# rack.net
KiCad netlist of a schematic drawn in EAGLE
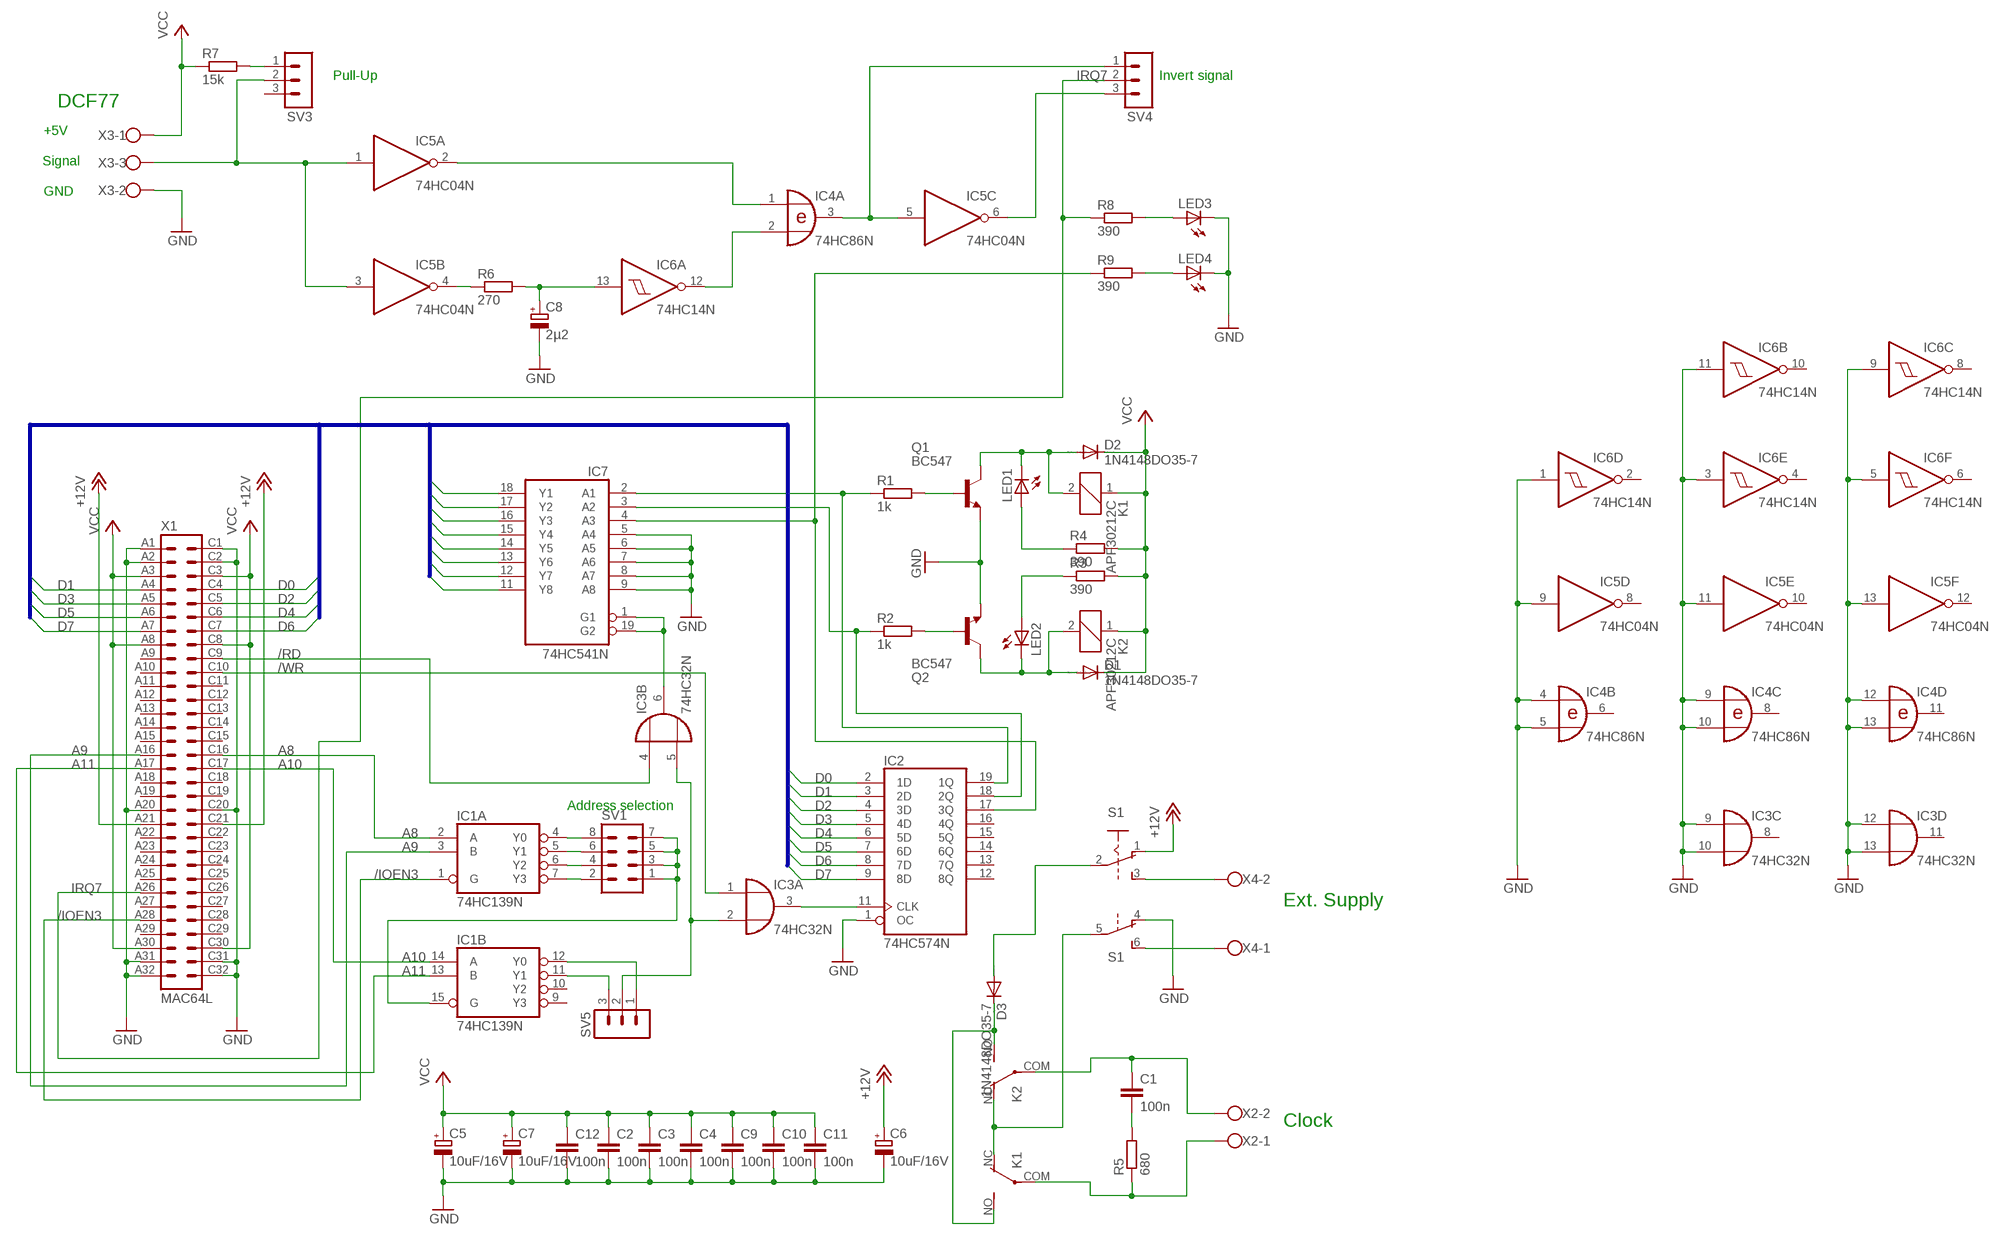
[diagram p0: schematic, sheet 1]

(export (version "E")
  (design (tool "Eeschema 10.0.6"))
  (components
    (comp (ref "C1")
      (value "100n")
      (footprint "eagle-import:C050-024X044")
      (libsource (lib "eagle-import") (part "C-EU050-024X044"))
    )
    (comp (ref "C2")
      (value "100n")
      (footprint "eagle-import:C050-024X044")
      (libsource (lib "eagle-import") (part "C-EU050-024X044"))
    )
    (comp (ref "C3")
      (value "100n")
      (footprint "eagle-import:C050-024X044")
      (libsource (lib "eagle-import") (part "C-EU050-024X044"))
    )
    (comp (ref "C4")
      (value "100n")
      (footprint "eagle-import:C050-024X044")
      (libsource (lib "eagle-import") (part "C-EU050-024X044"))
    )
    (comp (ref "C5")
      (value "10uF/16V")
      (footprint "eagle-import:TT2D5")
      (libsource (lib "eagle-import") (part "CPOL-EUTT2D5"))
    )
    (comp (ref "C6")
      (value "10uF/16V")
      (footprint "eagle-import:TT2D5")
      (libsource (lib "eagle-import") (part "CPOL-EUTT2D5"))
    )
    (comp (ref "C7")
      (value "10uF/16V")
      (footprint "eagle-import:TT2D5")
      (libsource (lib "eagle-import") (part "CPOL-EUTT2D5"))
    )
    (comp (ref "C8")
      (value "2µ2")
      (footprint "eagle-import:E2,5-6E")
      (libsource (lib "eagle-import") (part "CPOL-EUE2,5-6E"))
    )
    (comp (ref "C9")
      (value "100n")
      (footprint "eagle-import:C050-024X044")
      (libsource (lib "eagle-import") (part "C-EU050-024X044"))
    )
    (comp (ref "C10")
      (value "100n")
      (footprint "eagle-import:C050-024X044")
      (libsource (lib "eagle-import") (part "C-EU050-024X044"))
    )
    (comp (ref "C11")
      (value "100n")
      (footprint "eagle-import:C050-024X044")
      (libsource (lib "eagle-import") (part "C-EU050-024X044"))
    )
    (comp (ref "C12")
      (value "100n")
      (footprint "eagle-import:C050-024X044")
      (libsource (lib "eagle-import") (part "C-EU050-024X044"))
    )
    (comp (ref "D1")
      (value "1N4148DO35-7")
      (footprint "eagle-import:DO35-7")
      (libsource (lib "eagle-import") (part "1N4148DO35-7"))
    )
    (comp (ref "D2")
      (value "1N4148DO35-7")
      (footprint "eagle-import:DO35-7")
      (libsource (lib "eagle-import") (part "1N4148DO35-7"))
    )
    (comp (ref "D3")
      (value "1N4148DO35-7")
      (footprint "eagle-import:DO35-7")
      (libsource (lib "eagle-import") (part "1N4148DO35-7"))
    )
    (comp (ref "IC1")
      (value "74HC139N")
      (footprint "eagle-import:DIL16")
      (libsource (lib "eagle-import") (part "74139NHC"))
    )
    (comp (ref "IC2")
      (value "74HC574N")
      (footprint "eagle-import:DIL20")
      (libsource (lib "eagle-import") (part "74574NHC"))
    )
    (comp (ref "IC3")
      (value "74HC32N")
      (footprint "eagle-import:DIL14")
      (libsource (lib "eagle-import") (part "7432NHC"))
    )
    (comp (ref "IC4")
      (value "74HC86N")
      (footprint "eagle-import:DIL14")
      (libsource (lib "eagle-import") (part "7486NHC"))
    )
    (comp (ref "IC5")
      (value "74HC04N")
      (footprint "eagle-import:DIL14")
      (libsource (lib "eagle-import") (part "7404NHC"))
    )
    (comp (ref "IC6")
      (value "74HC14N")
      (footprint "eagle-import:DIL14")
      (libsource (lib "eagle-import") (part "7414NHC"))
    )
    (comp (ref "IC7")
      (value "74HC541N")
      (footprint "eagle-import:DIL20")
      (libsource (lib "eagle-import") (part "74541NHC"))
    )
    (comp (ref "K1")
      (value "APF30212C")
      (footprint "eagle-import:APF30212C")
      (libsource (lib "eagle-import") (part "APF30212C"))
    )
    (comp (ref "K2")
      (value "APF30212C")
      (footprint "eagle-import:APF30212C")
      (libsource (lib "eagle-import") (part "APF30212C"))
    )
    (comp (ref "LED1")
      (value "LEDB155")
      (footprint "eagle-import:Q62902-B155")
      (libsource (lib "eagle-import") (part "LEDB155"))
    )
    (comp (ref "LED2")
      (value "LEDB155")
      (footprint "eagle-import:Q62902-B155")
      (libsource (lib "eagle-import") (part "LEDB155"))
    )
    (comp (ref "LED3")
      (value "LEDB155")
      (footprint "eagle-import:Q62902-B155")
      (libsource (lib "eagle-import") (part "LEDB155"))
    )
    (comp (ref "LED4")
      (value "LEDB155")
      (footprint "eagle-import:Q62902-B155")
      (libsource (lib "eagle-import") (part "LEDB155"))
    )
    (comp (ref "Q1")
      (value "BC547")
      (footprint "eagle-import:TO92")
      (libsource (lib "eagle-import") (part "BC547"))
    )
    (comp (ref "Q2")
      (value "BC547")
      (footprint "eagle-import:TO92")
      (libsource (lib "eagle-import") (part "BC547"))
    )
    (comp (ref "R1")
      (value "1k")
      (footprint "eagle-import:0204_7")
      (libsource (lib "eagle-import") (part "R-EU_0204/7"))
    )
    (comp (ref "R2")
      (value "1k")
      (footprint "eagle-import:0204_7")
      (libsource (lib "eagle-import") (part "R-EU_0204/7"))
    )
    (comp (ref "R3")
      (value "390")
      (footprint "eagle-import:0204_7")
      (libsource (lib "eagle-import") (part "R-EU_0204/7"))
    )
    (comp (ref "R4")
      (value "390")
      (footprint "eagle-import:0204_7")
      (libsource (lib "eagle-import") (part "R-EU_0204/7"))
    )
    (comp (ref "R5")
      (value "680")
      (footprint "eagle-import:0204_7")
      (libsource (lib "eagle-import") (part "R-EU_0204/7"))
    )
    (comp (ref "R6")
      (value "270")
      (footprint "eagle-import:0204_7")
      (libsource (lib "eagle-import") (part "R-EU_0204/7"))
    )
    (comp (ref "R7")
      (value "15k")
      (footprint "eagle-import:0204_7")
      (libsource (lib "eagle-import") (part "R-EU_0204/7"))
    )
    (comp (ref "R8")
      (value "390")
      (footprint "eagle-import:0204_7")
      (libsource (lib "eagle-import") (part "R-EU_0204/7"))
    )
    (comp (ref "R9")
      (value "390")
      (footprint "eagle-import:0204_7")
      (libsource (lib "eagle-import") (part "R-EU_0204/7"))
    )
    (comp (ref "S1")
      (value "A68-A31")
      (footprint "eagle-import:A68-A31")
      (libsource (lib "eagle-import") (part "A68-A31"))
    )
    (comp (ref "SV1")
      (value "MA04-2")
      (footprint "eagle-import:MA04-2")
      (libsource (lib "eagle-import") (part "MA04-2"))
    )
    (comp (ref "SV3")
      (value "MA03-1")
      (footprint "eagle-import:MA03-1")
      (libsource (lib "eagle-import") (part "MA03-1"))
    )
    (comp (ref "SV4")
      (value "MA03-1")
      (footprint "eagle-import:MA03-1")
      (libsource (lib "eagle-import") (part "MA03-1"))
    )
    (comp (ref "SV5")
      (value "MA03-1")
      (footprint "eagle-import:MA03-1")
      (libsource (lib "eagle-import") (part "MA03-1"))
    )
    (comp (ref "X1")
      (value "MAC64L")
      (footprint "eagle-import:MAC64L")
      (libsource (lib "eagle-import") (part "MAC64L"))
    )
    (comp (ref "X2")
      (value "W237-102")
      (footprint "eagle-import:W237-102")
      (fields (field (name "MPN") "237-102"))
      (libsource (lib "eagle-import") (part "W237-102"))
    )
    (comp (ref "X3")
      (value "W237-103")
      (footprint "eagle-import:W237-103")
      (fields (field (name "MPN") "237-103"))
      (libsource (lib "eagle-import") (part "W237-103"))
    )
    (comp (ref "X4")
      (value "W237-102")
      (footprint "eagle-import:W237-102")
      (fields (field (name "MPN") "237-102"))
      (libsource (lib "eagle-import") (part "W237-102"))
    )
  )
  (nets
    (net (code "1") (name "+12V") (class "Default")
      (node (ref "C6") (pin "+") (pinfunction "+_+") (pintype "passive"))
      (node (ref "S1") (pin "1") (pinfunction "O_1") (pintype "passive"))
      (node (ref "X1") (pin "A21") (pinfunction "A21_A21") (pintype "passive"))
      (node (ref "X1") (pin "C21") (pinfunction "C21_C21") (pintype "passive"))
    )
    (net (code "2") (name "/A8") (class "Default")
      (node (ref "IC1") (pin "2") (pinfunction "A_2") (pintype "input"))
      (node (ref "X1") (pin "C16") (pinfunction "C16_C16") (pintype "passive"))
    )
    (net (code "3") (name "/A9") (class "Default")
      (node (ref "IC1") (pin "3") (pinfunction "B_3") (pintype "input"))
      (node (ref "X1") (pin "A16") (pinfunction "A16_A16") (pintype "passive"))
    )
    (net (code "4") (name "/A10") (class "Default")
      (node (ref "IC1") (pin "14") (pinfunction "A_14") (pintype "input"))
      (node (ref "X1") (pin "C17") (pinfunction "C17_C17") (pintype "passive"))
    )
    (net (code "5") (name "/A11") (class "Default")
      (node (ref "IC1") (pin "13") (pinfunction "B_13") (pintype "input"))
      (node (ref "X1") (pin "A17") (pinfunction "A17_A17") (pintype "passive"))
    )
    (net (code "6") (name "/D0") (class "Default")
      (node (ref "IC2") (pin "2") (pinfunction "1D_2") (pintype "input"))
      (node (ref "IC7") (pin "18") (pinfunction "Y1_18") (pintype "tri_state"))
      (node (ref "X1") (pin "C4") (pinfunction "C4_C4") (pintype "passive"))
    )
    (net (code "7") (name "/D1") (class "Default")
      (node (ref "IC2") (pin "3") (pinfunction "2D_3") (pintype "input"))
      (node (ref "IC7") (pin "17") (pinfunction "Y2_17") (pintype "tri_state"))
      (node (ref "X1") (pin "A4") (pinfunction "A4_A4") (pintype "passive"))
    )
    (net (code "8") (name "/D2") (class "Default")
      (node (ref "IC2") (pin "4") (pinfunction "3D_4") (pintype "input"))
      (node (ref "IC7") (pin "16") (pinfunction "Y3_16") (pintype "tri_state"))
      (node (ref "X1") (pin "C5") (pinfunction "C5_C5") (pintype "passive"))
    )
    (net (code "9") (name "/D3") (class "Default")
      (node (ref "IC2") (pin "5") (pinfunction "4D_5") (pintype "input"))
      (node (ref "IC7") (pin "15") (pinfunction "Y4_15") (pintype "tri_state"))
      (node (ref "X1") (pin "A5") (pinfunction "A5_A5") (pintype "passive"))
    )
    (net (code "10") (name "/D4") (class "Default")
      (node (ref "IC2") (pin "6") (pinfunction "5D_6") (pintype "input"))
      (node (ref "IC7") (pin "14") (pinfunction "Y5_14") (pintype "tri_state"))
      (node (ref "X1") (pin "C6") (pinfunction "C6_C6") (pintype "passive"))
    )
    (net (code "11") (name "/D5") (class "Default")
      (node (ref "IC2") (pin "7") (pinfunction "6D_7") (pintype "input"))
      (node (ref "IC7") (pin "13") (pinfunction "Y6_13") (pintype "tri_state"))
      (node (ref "X1") (pin "A6") (pinfunction "A6_A6") (pintype "passive"))
    )
    (net (code "12") (name "/D6") (class "Default")
      (node (ref "IC2") (pin "8") (pinfunction "7D_8") (pintype "input"))
      (node (ref "IC7") (pin "12") (pinfunction "Y7_12") (pintype "tri_state"))
      (node (ref "X1") (pin "C7") (pinfunction "C7_C7") (pintype "passive"))
    )
    (net (code "13") (name "/D7") (class "Default")
      (node (ref "IC2") (pin "9") (pinfunction "8D_9") (pintype "input"))
      (node (ref "IC7") (pin "11") (pinfunction "Y8_11") (pintype "tri_state"))
      (node (ref "X1") (pin "A7") (pinfunction "A7_A7") (pintype "passive"))
    )
    (net (code "14") (name "/IRQ7") (class "Default")
      (node (ref "R8") (pin "1") (pinfunction "1_1") (pintype "passive"))
      (node (ref "SV4") (pin "2") (pinfunction "2_2") (pintype "passive"))
      (node (ref "X1") (pin "A26") (pinfunction "A26_A26") (pintype "passive"))
    )
    (net (code "15") (name "/{slash}IOEN3") (class "Default")
      (node (ref "IC1") (pin "1") (pinfunction "G_1") (pintype "input"))
      (node (ref "X1") (pin "A28") (pinfunction "A28_A28") (pintype "passive"))
    )
    (net (code "16") (name "/{slash}RD") (class "Default")
      (node (ref "IC3") (pin "4") (pinfunction "I0_4") (pintype "input"))
      (node (ref "X1") (pin "C9") (pinfunction "C9_C9") (pintype "passive"))
    )
    (net (code "17") (name "/{slash}WR") (class "Default")
      (node (ref "IC3") (pin "1") (pinfunction "I0_1") (pintype "input"))
      (node (ref "X1") (pin "C10") (pinfunction "C10_C10") (pintype "passive"))
    )
    (net (code "18") (name "GND") (class "Default")
      (node (ref "C10") (pin "2") (pinfunction "2_2") (pintype "passive"))
      (node (ref "C11") (pin "2") (pinfunction "2_2") (pintype "passive"))
      (node (ref "C12") (pin "2") (pinfunction "2_2") (pintype "passive"))
      (node (ref "C2") (pin "2") (pinfunction "2_2") (pintype "passive"))
      (node (ref "C3") (pin "2") (pinfunction "2_2") (pintype "passive"))
      (node (ref "C4") (pin "2") (pinfunction "2_2") (pintype "passive"))
      (node (ref "C5") (pin "-") (pinfunction "-_-") (pintype "passive"))
      (node (ref "C6") (pin "-") (pinfunction "-_-") (pintype "passive"))
      (node (ref "C7") (pin "-") (pinfunction "-_-") (pintype "passive"))
      (node (ref "C8") (pin "-") (pinfunction "-_-") (pintype "passive"))
      (node (ref "C9") (pin "2") (pinfunction "2_2") (pintype "passive"))
      (node (ref "IC2") (pin "1") (pinfunction "OC_1") (pintype "input"))
      (node (ref "IC3") (pin "10") (pinfunction "I1_10") (pintype "input"))
      (node (ref "IC3") (pin "12") (pinfunction "I0_12") (pintype "input"))
      (node (ref "IC3") (pin "13") (pinfunction "I1_13") (pintype "input"))
      (node (ref "IC3") (pin "9") (pinfunction "I0_9") (pintype "input"))
      (node (ref "IC4") (pin "10") (pinfunction "I1_10") (pintype "input"))
      (node (ref "IC4") (pin "12") (pinfunction "I0_12") (pintype "input"))
      (node (ref "IC4") (pin "13") (pinfunction "I1_13") (pintype "input"))
      (node (ref "IC4") (pin "4") (pinfunction "I0_4") (pintype "input"))
      (node (ref "IC4") (pin "5") (pinfunction "I1_5") (pintype "input"))
      (node (ref "IC4") (pin "9") (pinfunction "I0_9") (pintype "input"))
      (node (ref "IC5") (pin "11") (pinfunction "I_11") (pintype "input"))
      (node (ref "IC5") (pin "13") (pinfunction "I_13") (pintype "input"))
      (node (ref "IC5") (pin "9") (pinfunction "I_9") (pintype "input"))
      (node (ref "IC6") (pin "1") (pinfunction "I_1") (pintype "input"))
      (node (ref "IC6") (pin "11") (pinfunction "I_11") (pintype "input"))
      (node (ref "IC6") (pin "3") (pinfunction "I_3") (pintype "input"))
      (node (ref "IC6") (pin "5") (pinfunction "I_5") (pintype "input"))
      (node (ref "IC6") (pin "9") (pinfunction "I_9") (pintype "input"))
      (node (ref "IC7") (pin "5") (pinfunction "A4_5") (pintype "input"))
      (node (ref "IC7") (pin "6") (pinfunction "A5_6") (pintype "input"))
      (node (ref "IC7") (pin "7") (pinfunction "A6_7") (pintype "input"))
      (node (ref "IC7") (pin "8") (pinfunction "A7_8") (pintype "input"))
      (node (ref "IC7") (pin "9") (pinfunction "A8_9") (pintype "input"))
      (node (ref "LED3") (pin "K") (pinfunction "C_K") (pintype "passive"))
      (node (ref "LED4") (pin "K") (pinfunction "C_K") (pintype "passive"))
      (node (ref "Q1") (pin "1") (pinfunction "E_1") (pintype "passive"))
      (node (ref "Q2") (pin "1") (pinfunction "E_1") (pintype "passive"))
      (node (ref "S1") (pin "4") (pinfunction "O_4") (pintype "passive"))
      (node (ref "X1") (pin "A1") (pinfunction "A1_A1") (pintype "passive"))
      (node (ref "X1") (pin "A2") (pinfunction "A2_A2") (pintype "passive"))
      (node (ref "X1") (pin "A20") (pinfunction "A20_A20") (pintype "passive"))
      (node (ref "X1") (pin "A31") (pinfunction "A31_A31") (pintype "passive"))
      (node (ref "X1") (pin "A32") (pinfunction "A32_A32") (pintype "passive"))
      (node (ref "X1") (pin "C1") (pinfunction "C1_C1") (pintype "passive"))
      (node (ref "X1") (pin "C2") (pinfunction "C2_C2") (pintype "passive"))
      (node (ref "X1") (pin "C20") (pinfunction "C20_C20") (pintype "passive"))
      (node (ref "X1") (pin "C31") (pinfunction "C31_C31") (pintype "passive"))
      (node (ref "X1") (pin "C32") (pinfunction "C32_C32") (pintype "passive"))
      (node (ref "X3") (pin "2") (pinfunction "KL_2") (pintype "passive"))
    )
    (net (code "19") (name "Net-(C1-Pad2)") (class "Default")
      (node (ref "C1") (pin "2") (pinfunction "2_2") (pintype "passive"))
      (node (ref "R5") (pin "2") (pinfunction "2_2") (pintype "passive"))
    )
    (net (code "20") (name "Net-(IC1A-Y0)") (class "Default")
      (node (ref "IC1") (pin "4") (pinfunction "Y0_4") (pintype "output"))
      (node (ref "SV1") (pin "8") (pinfunction "8_8") (pintype "passive"))
    )
    (net (code "21") (name "Net-(IC1A-Y1)") (class "Default")
      (node (ref "IC1") (pin "5") (pinfunction "Y1_5") (pintype "output"))
      (node (ref "SV1") (pin "6") (pinfunction "6_6") (pintype "passive"))
    )
    (net (code "22") (name "Net-(IC1A-Y2)") (class "Default")
      (node (ref "IC1") (pin "6") (pinfunction "Y2_6") (pintype "output"))
      (node (ref "SV1") (pin "4") (pinfunction "4_4") (pintype "passive"))
    )
    (net (code "23") (name "Net-(IC1A-Y3)") (class "Default")
      (node (ref "IC1") (pin "7") (pinfunction "Y3_7") (pintype "output"))
      (node (ref "SV1") (pin "2") (pinfunction "2_2") (pintype "passive"))
    )
    (net (code "24") (name "Net-(IC1B-G)") (class "Default")
      (node (ref "IC1") (pin "15") (pinfunction "G_15") (pintype "input"))
      (node (ref "SV1") (pin "1") (pinfunction "1_1") (pintype "passive"))
      (node (ref "SV1") (pin "3") (pinfunction "3_3") (pintype "passive"))
      (node (ref "SV1") (pin "5") (pinfunction "5_5") (pintype "passive"))
      (node (ref "SV1") (pin "7") (pinfunction "7_7") (pintype "passive"))
    )
    (net (code "25") (name "Net-(IC1B-Y0)") (class "Default")
      (node (ref "IC1") (pin "12") (pinfunction "Y0_12") (pintype "output"))
      (node (ref "SV5") (pin "1") (pinfunction "1_1") (pintype "passive"))
    )
    (net (code "26") (name "Net-(IC1B-Y1)") (class "Default")
      (node (ref "IC1") (pin "11") (pinfunction "Y1_11") (pintype "output"))
      (node (ref "SV5") (pin "3") (pinfunction "3_3") (pintype "passive"))
    )
    (net (code "27") (name "Net-(IC2A-1Q)") (class "Default")
      (node (ref "IC2") (pin "19") (pinfunction "1Q_19") (pintype "tri_state"))
      (node (ref "IC7") (pin "2") (pinfunction "A1_2") (pintype "input"))
      (node (ref "R1") (pin "1") (pinfunction "1_1") (pintype "passive"))
    )
    (net (code "28") (name "Net-(IC2A-2Q)") (class "Default")
      (node (ref "IC2") (pin "18") (pinfunction "2Q_18") (pintype "tri_state"))
      (node (ref "IC7") (pin "3") (pinfunction "A2_3") (pintype "input"))
      (node (ref "R2") (pin "1") (pinfunction "1_1") (pintype "passive"))
    )
    (net (code "29") (name "Net-(IC2A-3Q)") (class "Default")
      (node (ref "IC2") (pin "17") (pinfunction "3Q_17") (pintype "tri_state"))
      (node (ref "IC7") (pin "4") (pinfunction "A3_4") (pintype "input"))
      (node (ref "R9") (pin "1") (pinfunction "1_1") (pintype "passive"))
    )
    (net (code "30") (name "Net-(IC2A-CLK)") (class "Default")
      (node (ref "IC2") (pin "11") (pinfunction "CLK_11") (pintype "input"))
      (node (ref "IC3") (pin "3") (pinfunction "O_3") (pintype "output"))
    )
    (net (code "31") (name "Net-(IC3A-I1)") (class "Default")
      (node (ref "IC3") (pin "2") (pinfunction "I1_2") (pintype "input"))
      (node (ref "IC3") (pin "5") (pinfunction "I1_5") (pintype "input"))
      (node (ref "SV5") (pin "2") (pinfunction "2_2") (pintype "passive"))
    )
    (net (code "32") (name "Net-(IC3B-O)") (class "Default")
      (node (ref "IC3") (pin "6") (pinfunction "O_6") (pintype "output"))
      (node (ref "IC7") (pin "1") (pinfunction "G1_1") (pintype "input"))
      (node (ref "IC7") (pin "19") (pinfunction "G2_19") (pintype "input"))
    )
    (net (code "33") (name "Net-(IC4A-I0)") (class "Default")
      (node (ref "IC4") (pin "1") (pinfunction "I0_1") (pintype "input"))
      (node (ref "IC5") (pin "2") (pinfunction "O_2") (pintype "output"))
    )
    (net (code "34") (name "Net-(IC4A-I1)") (class "Default")
      (node (ref "IC4") (pin "2") (pinfunction "I1_2") (pintype "input"))
      (node (ref "IC6") (pin "12") (pinfunction "O_12") (pintype "output"))
    )
    (net (code "35") (name "Net-(IC4A-O)") (class "Default")
      (node (ref "IC4") (pin "3") (pinfunction "O_3") (pintype "output"))
      (node (ref "IC5") (pin "5") (pinfunction "I_5") (pintype "input"))
      (node (ref "SV4") (pin "1") (pinfunction "1_1") (pintype "passive"))
    )
    (net (code "36") (name "Net-(IC5A-I)") (class "Default")
      (node (ref "IC5") (pin "1") (pinfunction "I_1") (pintype "input"))
      (node (ref "IC5") (pin "3") (pinfunction "I_3") (pintype "input"))
      (node (ref "SV3") (pin "2") (pinfunction "2_2") (pintype "passive"))
      (node (ref "X3") (pin "3") (pinfunction "KL_3") (pintype "passive"))
    )
    (net (code "37") (name "Net-(IC5B-O)") (class "Default")
      (node (ref "IC5") (pin "4") (pinfunction "O_4") (pintype "output"))
      (node (ref "R6") (pin "1") (pinfunction "1_1") (pintype "passive"))
    )
    (net (code "38") (name "Net-(IC5C-O)") (class "Default")
      (node (ref "IC5") (pin "6") (pinfunction "O_6") (pintype "output"))
      (node (ref "SV4") (pin "3") (pinfunction "3_3") (pintype "passive"))
    )
    (net (code "39") (name "Net-(IC6A-I)") (class "Default")
      (node (ref "C8") (pin "+") (pinfunction "+_+") (pintype "passive"))
      (node (ref "IC6") (pin "13") (pinfunction "I_13") (pintype "input"))
      (node (ref "R6") (pin "2") (pinfunction "2_2") (pintype "passive"))
    )
    (net (code "40") (name "Net-(K1B-O)") (class "Default")
      (node (ref "K1") (pin "NC") (pinfunction "O_NC") (pintype "passive"))
      (node (ref "K2") (pin "NC") (pinfunction "O_NC") (pintype "passive"))
      (node (ref "S1") (pin "5") (pinfunction "P_5") (pintype "passive"))
    )
    (net (code "41") (name "Net-(K1B-P)") (class "Default")
      (node (ref "K1") (pin "COM") (pinfunction "P_COM") (pintype "passive"))
      (node (ref "R5") (pin "1") (pinfunction "1_1") (pintype "passive"))
      (node (ref "X2") (pin "1") (pinfunction "KL_1") (pintype "passive"))
    )
    (net (code "42") (name "Net-(K1B-S)") (class "Default")
      (node (ref "D3") (pin "C") (pinfunction "C_C") (pintype "passive"))
      (node (ref "K1") (pin "NO") (pinfunction "S_NO") (pintype "passive"))
      (node (ref "K2") (pin "NO") (pinfunction "S_NO") (pintype "passive"))
    )
    (net (code "43") (name "Net-(K2B-P)") (class "Default")
      (node (ref "C1") (pin "1") (pinfunction "1_1") (pintype "passive"))
      (node (ref "K2") (pin "COM") (pinfunction "P_COM") (pintype "passive"))
      (node (ref "X2") (pin "2") (pinfunction "KL_2") (pintype "passive"))
    )
    (net (code "44") (name "Net-(LED1-C)") (class "Default")
      (node (ref "D2") (pin "A") (pinfunction "A_A") (pintype "passive"))
      (node (ref "K1") (pin "2") (pinfunction "2_2") (pintype "passive"))
      (node (ref "LED1") (pin "K") (pinfunction "C_K") (pintype "passive"))
      (node (ref "Q1") (pin "3") (pinfunction "C_3") (pintype "passive"))
    )
    (net (code "45") (name "Net-(LED1-PadA)") (class "Default")
      (node (ref "LED1") (pin "A") (pinfunction "A_A") (pintype "passive"))
      (node (ref "R4") (pin "1") (pinfunction "1_1") (pintype "passive"))
    )
    (net (code "46") (name "Net-(LED2-C)") (class "Default")
      (node (ref "D1") (pin "A") (pinfunction "A_A") (pintype "passive"))
      (node (ref "K2") (pin "2") (pinfunction "2_2") (pintype "passive"))
      (node (ref "LED2") (pin "K") (pinfunction "C_K") (pintype "passive"))
      (node (ref "Q2") (pin "3") (pinfunction "C_3") (pintype "passive"))
    )
    (net (code "47") (name "Net-(LED2-PadA)") (class "Default")
      (node (ref "LED2") (pin "A") (pinfunction "A_A") (pintype "passive"))
      (node (ref "R3") (pin "1") (pinfunction "1_1") (pintype "passive"))
    )
    (net (code "48") (name "Net-(LED3-PadA)") (class "Default")
      (node (ref "LED3") (pin "A") (pinfunction "A_A") (pintype "passive"))
      (node (ref "R8") (pin "2") (pinfunction "2_2") (pintype "passive"))
    )
    (net (code "49") (name "Net-(LED4-PadA)") (class "Default")
      (node (ref "LED4") (pin "A") (pinfunction "A_A") (pintype "passive"))
      (node (ref "R9") (pin "2") (pinfunction "2_2") (pintype "passive"))
    )
    (net (code "50") (name "Net-(Q1-B)") (class "Default")
      (node (ref "Q1") (pin "2") (pinfunction "B_2") (pintype "passive"))
      (node (ref "R1") (pin "2") (pinfunction "2_2") (pintype "passive"))
    )
    (net (code "51") (name "Net-(Q2-B)") (class "Default")
      (node (ref "Q2") (pin "2") (pinfunction "B_2") (pintype "passive"))
      (node (ref "R2") (pin "2") (pinfunction "2_2") (pintype "passive"))
    )
    (net (code "52") (name "Net-(R7-Pad2)") (class "Default")
      (node (ref "R7") (pin "2") (pinfunction "2_2") (pintype "passive"))
      (node (ref "SV3") (pin "1") (pinfunction "1_1") (pintype "passive"))
    )
    (net (code "53") (name "Net-(S1A-P)") (class "Default")
      (node (ref "D3") (pin "A") (pinfunction "A_A") (pintype "passive"))
      (node (ref "S1") (pin "2") (pinfunction "P_2") (pintype "passive"))
    )
    (net (code "54") (name "Net-(S1A-S)") (class "Default")
      (node (ref "S1") (pin "3") (pinfunction "S_3") (pintype "passive"))
      (node (ref "X4") (pin "2") (pinfunction "KL_2") (pintype "passive"))
    )
    (net (code "55") (name "Net-(S1B-S)") (class "Default")
      (node (ref "S1") (pin "6") (pinfunction "S_6") (pintype "passive"))
      (node (ref "X4") (pin "1") (pinfunction "KL_1") (pintype "passive"))
    )
    (net (code "56") (name "VCC") (class "Default")
      (node (ref "C10") (pin "1") (pinfunction "1_1") (pintype "passive"))
      (node (ref "C11") (pin "1") (pinfunction "1_1") (pintype "passive"))
      (node (ref "C12") (pin "1") (pinfunction "1_1") (pintype "passive"))
      (node (ref "C2") (pin "1") (pinfunction "1_1") (pintype "passive"))
      (node (ref "C3") (pin "1") (pinfunction "1_1") (pintype "passive"))
      (node (ref "C4") (pin "1") (pinfunction "1_1") (pintype "passive"))
      (node (ref "C5") (pin "+") (pinfunction "+_+") (pintype "passive"))
      (node (ref "C7") (pin "+") (pinfunction "+_+") (pintype "passive"))
      (node (ref "C9") (pin "1") (pinfunction "1_1") (pintype "passive"))
      (node (ref "D1") (pin "C") (pinfunction "C_C") (pintype "passive"))
      (node (ref "D2") (pin "C") (pinfunction "C_C") (pintype "passive"))
      (node (ref "K1") (pin "1") (pinfunction "1_1") (pintype "passive"))
      (node (ref "K2") (pin "1") (pinfunction "1_1") (pintype "passive"))
      (node (ref "R3") (pin "2") (pinfunction "2_2") (pintype "passive"))
      (node (ref "R4") (pin "2") (pinfunction "2_2") (pintype "passive"))
      (node (ref "R7") (pin "1") (pinfunction "1_1") (pintype "passive"))
      (node (ref "X1") (pin "A3") (pinfunction "A3_A3") (pintype "passive"))
      (node (ref "X1") (pin "A30") (pinfunction "A30_A30") (pintype "passive"))
      (node (ref "X1") (pin "A8") (pinfunction "A8_A8") (pintype "passive"))
      (node (ref "X1") (pin "C3") (pinfunction "C3_C3") (pintype "passive"))
      (node (ref "X1") (pin "C30") (pinfunction "C30_C30") (pintype "passive"))
      (node (ref "X1") (pin "C8") (pinfunction "C8_C8") (pintype "passive"))
      (node (ref "X3") (pin "1") (pinfunction "KL_1") (pintype "passive"))
    )
    (net (code "57") (name "unconnected-(IC1B-Y2-Pad10)") (class "Default")
      (node (ref "IC1") (pin "10") (pinfunction "Y2_10") (pintype "output"))
    )
    (net (code "58") (name "unconnected-(IC1B-Y3-Pad9)") (class "Default")
      (node (ref "IC1") (pin "9") (pinfunction "Y3_9") (pintype "output"))
    )
    (net (code "59") (name "unconnected-(IC2A-4Q-Pad16)") (class "Default")
      (node (ref "IC2") (pin "16") (pinfunction "4Q_16") (pintype "tri_state"))
    )
    (net (code "60") (name "unconnected-(IC2A-5Q-Pad15)") (class "Default")
      (node (ref "IC2") (pin "15") (pinfunction "5Q_15") (pintype "tri_state"))
    )
    (net (code "61") (name "unconnected-(IC2A-6Q-Pad14)") (class "Default")
      (node (ref "IC2") (pin "14") (pinfunction "6Q_14") (pintype "tri_state"))
    )
    (net (code "62") (name "unconnected-(IC2A-7Q-Pad13)") (class "Default")
      (node (ref "IC2") (pin "13") (pinfunction "7Q_13") (pintype "tri_state"))
    )
    (net (code "63") (name "unconnected-(IC2A-8Q-Pad12)") (class "Default")
      (node (ref "IC2") (pin "12") (pinfunction "8Q_12") (pintype "tri_state"))
    )
    (net (code "64") (name "unconnected-(IC3C-O-Pad8)") (class "Default")
      (node (ref "IC3") (pin "8") (pinfunction "O_8") (pintype "output"))
    )
    (net (code "65") (name "unconnected-(IC3D-O-Pad11)") (class "Default")
      (node (ref "IC3") (pin "11") (pinfunction "O_11") (pintype "output"))
    )
    (net (code "66") (name "unconnected-(IC4B-O-Pad6)") (class "Default")
      (node (ref "IC4") (pin "6") (pinfunction "O_6") (pintype "output"))
    )
    (net (code "67") (name "unconnected-(IC4C-O-Pad8)") (class "Default")
      (node (ref "IC4") (pin "8") (pinfunction "O_8") (pintype "output"))
    )
    (net (code "68") (name "unconnected-(IC4D-O-Pad11)") (class "Default")
      (node (ref "IC4") (pin "11") (pinfunction "O_11") (pintype "output"))
    )
    (net (code "69") (name "unconnected-(IC5D-O-Pad8)") (class "Default")
      (node (ref "IC5") (pin "8") (pinfunction "O_8") (pintype "output"))
    )
    (net (code "70") (name "unconnected-(IC5E-O-Pad10)") (class "Default")
      (node (ref "IC5") (pin "10") (pinfunction "O_10") (pintype "output"))
    )
    (net (code "71") (name "unconnected-(IC5F-O-Pad12)") (class "Default")
      (node (ref "IC5") (pin "12") (pinfunction "O_12") (pintype "output"))
    )
    (net (code "72") (name "unconnected-(IC6B-O-Pad10)") (class "Default")
      (node (ref "IC6") (pin "10") (pinfunction "O_10") (pintype "output"))
    )
    (net (code "73") (name "unconnected-(IC6C-O-Pad8)") (class "Default")
      (node (ref "IC6") (pin "8") (pinfunction "O_8") (pintype "output"))
    )
    (net (code "74") (name "unconnected-(IC6D-O-Pad2)") (class "Default")
      (node (ref "IC6") (pin "2") (pinfunction "O_2") (pintype "output"))
    )
    (net (code "75") (name "unconnected-(IC6E-O-Pad4)") (class "Default")
      (node (ref "IC6") (pin "4") (pinfunction "O_4") (pintype "output"))
    )
    (net (code "76") (name "unconnected-(IC6F-O-Pad6)") (class "Default")
      (node (ref "IC6") (pin "6") (pinfunction "O_6") (pintype "output"))
    )
    (net (code "77") (name "unconnected-(SV3-Pad3)") (class "Default")
      (node (ref "SV3") (pin "3") (pinfunction "3_3") (pintype "passive"))
    )
    (net (code "78") (name "unconnected-(X1-PadA9)") (class "Default")
      (node (ref "X1") (pin "A9") (pinfunction "A9_A9") (pintype "passive"))
    )
    (net (code "79") (name "unconnected-(X1-PadA10)") (class "Default")
      (node (ref "X1") (pin "A10") (pinfunction "A10_A10") (pintype "passive"))
    )
    (net (code "80") (name "unconnected-(X1-PadA11)") (class "Default")
      (node (ref "X1") (pin "A11") (pinfunction "A11_A11") (pintype "passive"))
    )
    (net (code "81") (name "unconnected-(X1-PadA12)") (class "Default")
      (node (ref "X1") (pin "A12") (pinfunction "A12_A12") (pintype "passive"))
    )
    (net (code "82") (name "unconnected-(X1-PadA13)") (class "Default")
      (node (ref "X1") (pin "A13") (pinfunction "A13_A13") (pintype "passive"))
    )
    (net (code "83") (name "unconnected-(X1-PadA14)") (class "Default")
      (node (ref "X1") (pin "A14") (pinfunction "A14_A14") (pintype "passive"))
    )
    (net (code "84") (name "unconnected-(X1-PadA15)") (class "Default")
      (node (ref "X1") (pin "A15") (pinfunction "A15_A15") (pintype "passive"))
    )
    (net (code "85") (name "unconnected-(X1-PadA18)") (class "Default")
      (node (ref "X1") (pin "A18") (pinfunction "A18_A18") (pintype "passive"))
    )
    (net (code "86") (name "unconnected-(X1-PadA19)") (class "Default")
      (node (ref "X1") (pin "A19") (pinfunction "A19_A19") (pintype "passive"))
    )
    (net (code "87") (name "unconnected-(X1-PadA22)") (class "Default")
      (node (ref "X1") (pin "A22") (pinfunction "A22_A22") (pintype "passive"))
    )
    (net (code "88") (name "unconnected-(X1-PadA23)") (class "Default")
      (node (ref "X1") (pin "A23") (pinfunction "A23_A23") (pintype "passive"))
    )
    (net (code "89") (name "unconnected-(X1-PadA24)") (class "Default")
      (node (ref "X1") (pin "A24") (pinfunction "A24_A24") (pintype "passive"))
    )
    (net (code "90") (name "unconnected-(X1-PadA25)") (class "Default")
      (node (ref "X1") (pin "A25") (pinfunction "A25_A25") (pintype "passive"))
    )
    (net (code "91") (name "unconnected-(X1-PadA27)") (class "Default")
      (node (ref "X1") (pin "A27") (pinfunction "A27_A27") (pintype "passive"))
    )
    (net (code "92") (name "unconnected-(X1-PadA29)") (class "Default")
      (node (ref "X1") (pin "A29") (pinfunction "A29_A29") (pintype "passive"))
    )
    (net (code "93") (name "unconnected-(X1-PadC11)") (class "Default")
      (node (ref "X1") (pin "C11") (pinfunction "C11_C11") (pintype "passive"))
    )
    (net (code "94") (name "unconnected-(X1-PadC12)") (class "Default")
      (node (ref "X1") (pin "C12") (pinfunction "C12_C12") (pintype "passive"))
    )
    (net (code "95") (name "unconnected-(X1-PadC13)") (class "Default")
      (node (ref "X1") (pin "C13") (pinfunction "C13_C13") (pintype "passive"))
    )
    (net (code "96") (name "unconnected-(X1-PadC14)") (class "Default")
      (node (ref "X1") (pin "C14") (pinfunction "C14_C14") (pintype "passive"))
    )
    (net (code "97") (name "unconnected-(X1-PadC15)") (class "Default")
      (node (ref "X1") (pin "C15") (pinfunction "C15_C15") (pintype "passive"))
    )
    (net (code "98") (name "unconnected-(X1-PadC18)") (class "Default")
      (node (ref "X1") (pin "C18") (pinfunction "C18_C18") (pintype "passive"))
    )
    (net (code "99") (name "unconnected-(X1-PadC19)") (class "Default")
      (node (ref "X1") (pin "C19") (pinfunction "C19_C19") (pintype "passive"))
    )
    (net (code "100") (name "unconnected-(X1-PadC22)") (class "Default")
      (node (ref "X1") (pin "C22") (pinfunction "C22_C22") (pintype "passive"))
    )
    (net (code "101") (name "unconnected-(X1-PadC23)") (class "Default")
      (node (ref "X1") (pin "C23") (pinfunction "C23_C23") (pintype "passive"))
    )
    (net (code "102") (name "unconnected-(X1-PadC24)") (class "Default")
      (node (ref "X1") (pin "C24") (pinfunction "C24_C24") (pintype "passive"))
    )
    (net (code "103") (name "unconnected-(X1-PadC25)") (class "Default")
      (node (ref "X1") (pin "C25") (pinfunction "C25_C25") (pintype "passive"))
    )
    (net (code "104") (name "unconnected-(X1-PadC26)") (class "Default")
      (node (ref "X1") (pin "C26") (pinfunction "C26_C26") (pintype "passive"))
    )
    (net (code "105") (name "unconnected-(X1-PadC27)") (class "Default")
      (node (ref "X1") (pin "C27") (pinfunction "C27_C27") (pintype "passive"))
    )
    (net (code "106") (name "unconnected-(X1-PadC28)") (class "Default")
      (node (ref "X1") (pin "C28") (pinfunction "C28_C28") (pintype "passive"))
    )
    (net (code "107") (name "unconnected-(X1-PadC29)") (class "Default")
      (node (ref "X1") (pin "C29") (pinfunction "C29_C29") (pintype "passive"))
    )
  )
)
